# Y1BVER2_0_1.net
KiCad netlist of a schematic drawn in Altium Designer
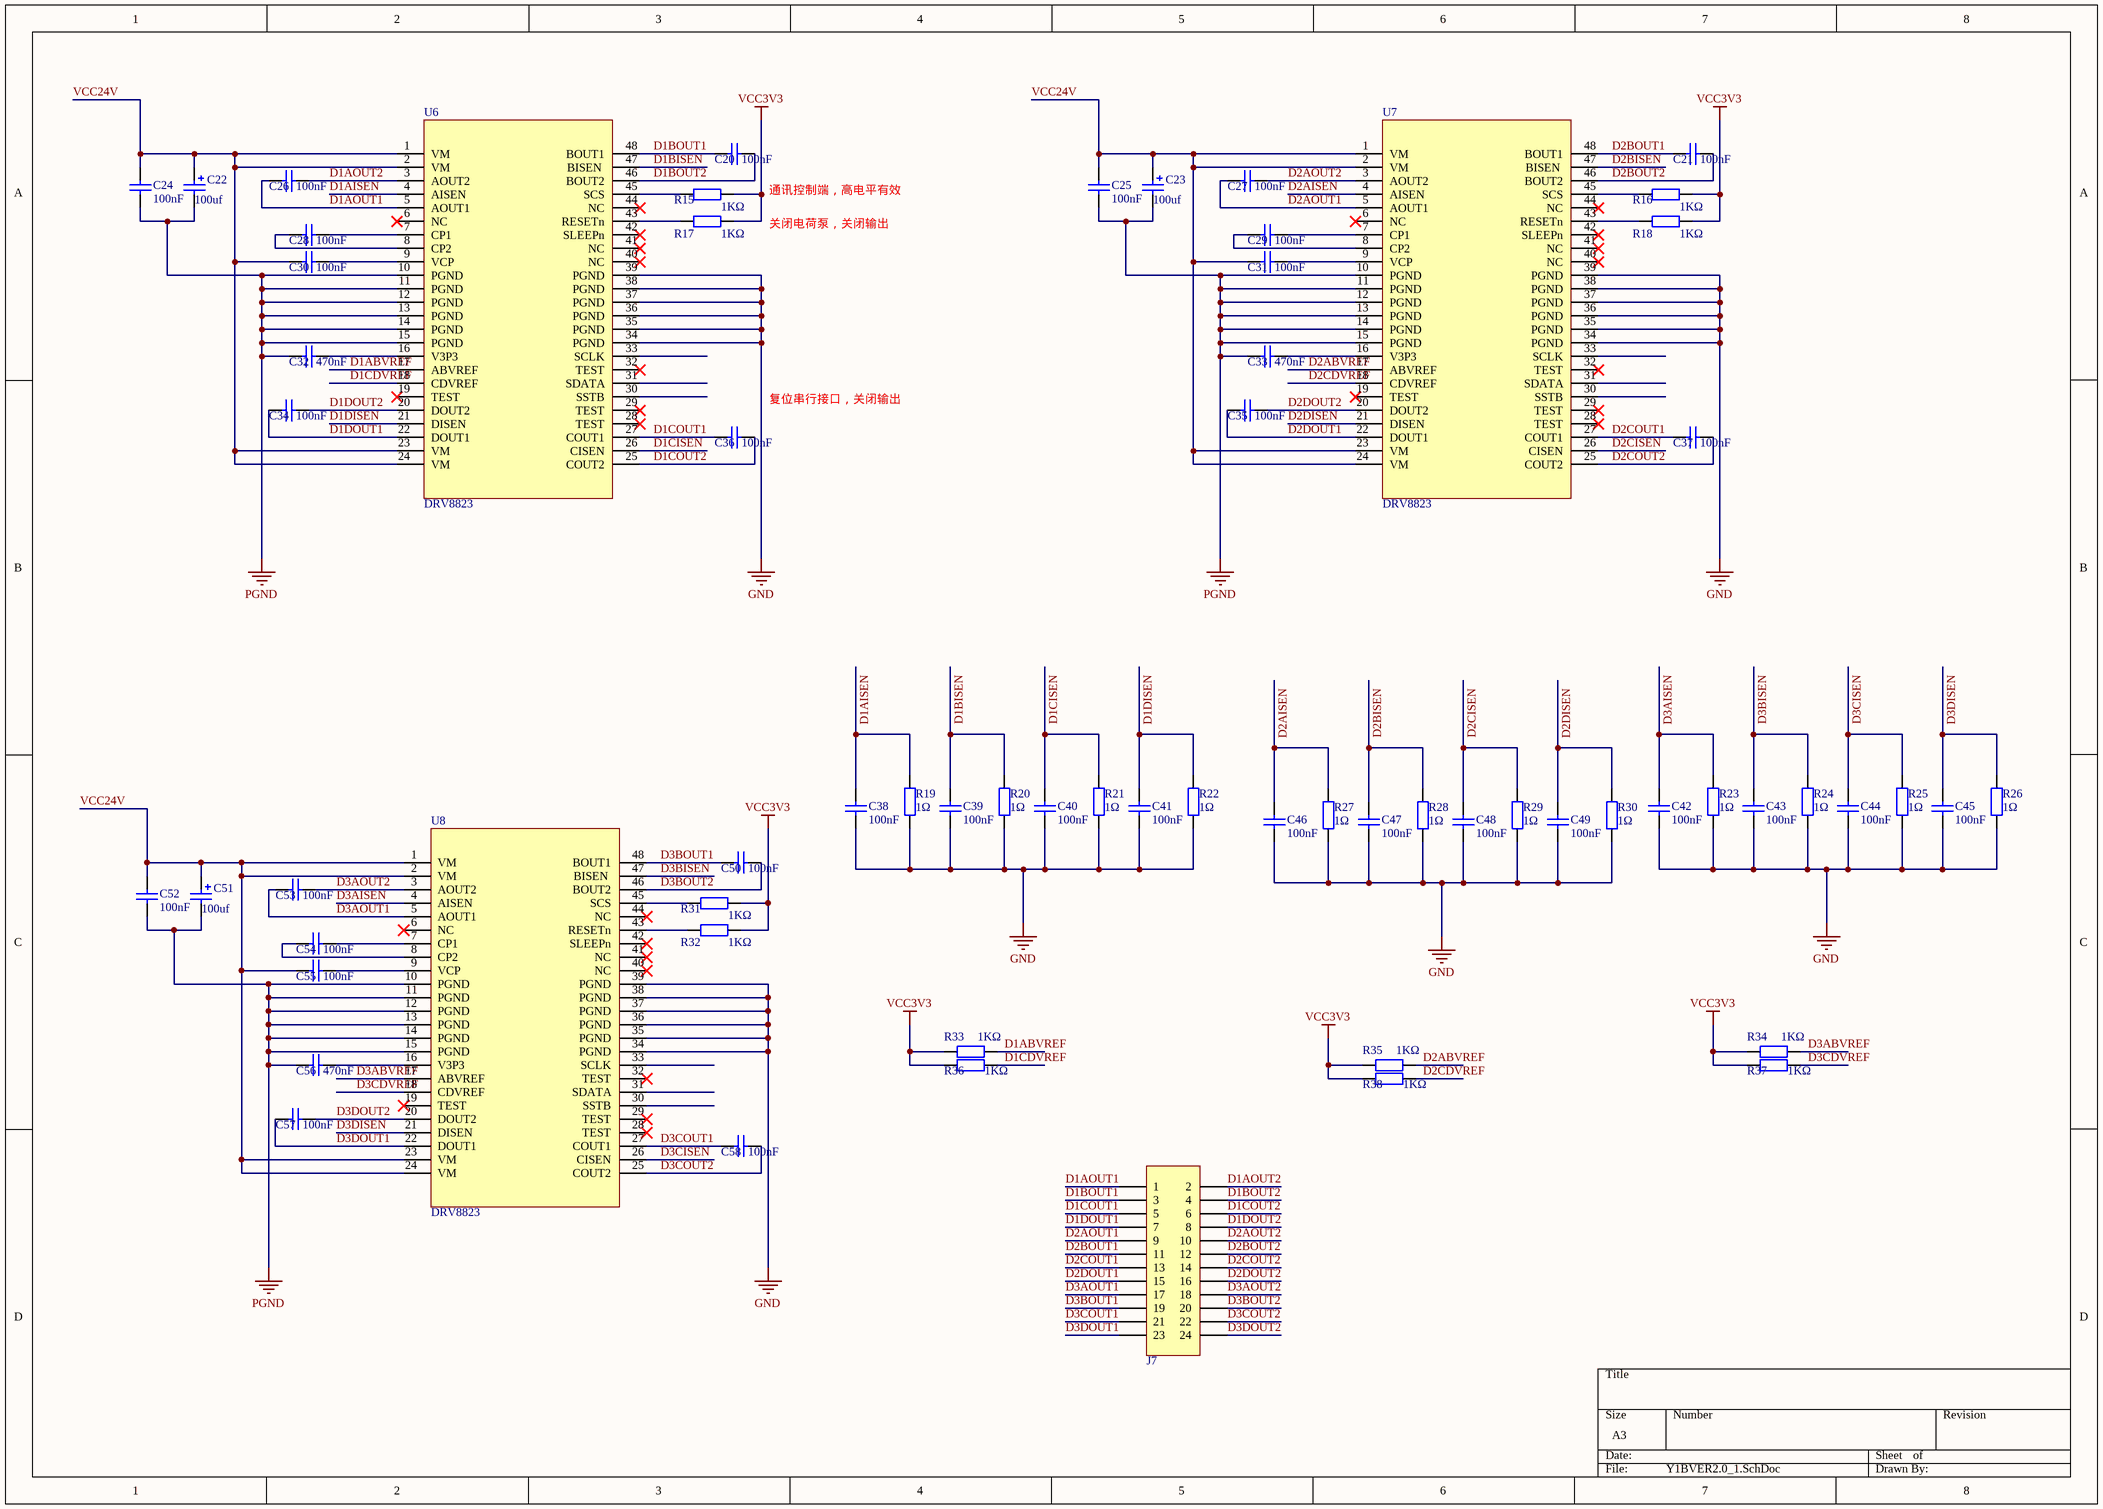
[diagram p0: Y1BVER2.0_1.SchDoc]

(export (version "E")
  (design (tool "Eeschema 10.0.6"))
  (components
    (comp (ref "C20")
      (value "100nF")
      (footprint "0603_C")
      (description "贴片电容")
      (libsource (lib "AD封装2018.9.19Miscellaneous Devices LC") (part "0603 100nF (104) 10% 50V"))
    )
    (comp (ref "C21")
      (value "100nF")
      (footprint "0603_C")
      (description "贴片电容")
      (libsource (lib "AD封装2018.9.19Miscellaneous Devices LC") (part "0603 100nF (104) 10% 50V"))
    )
    (comp (ref "C22") (value "100uf") (footprint "E_6.3*5.4") (libsource (lib "我的集成库") (part "C")))
    (comp (ref "C23") (value "100uf") (footprint "E_6.3*5.4") (libsource (lib "我的集成库") (part "C")))
    (comp (ref "C24")
      (value "100nF")
      (footprint "0603_C")
      (description "贴片电容")
      (libsource (lib "AD封装2018.9.19Miscellaneous Devices LC") (part "0603 100nF (104) 10% 50V"))
    )
    (comp (ref "C25")
      (value "100nF")
      (footprint "0603_C")
      (description "贴片电容")
      (libsource (lib "AD封装2018.9.19Miscellaneous Devices LC") (part "0603 100nF (104) 10% 50V"))
    )
    (comp (ref "C26")
      (value "100nF")
      (footprint "0603_C")
      (description "贴片电容")
      (libsource (lib "AD封装2018.9.19Miscellaneous Devices LC") (part "0603 100nF (104) 10% 50V"))
    )
    (comp (ref "C27")
      (value "100nF")
      (footprint "0603_C")
      (description "贴片电容")
      (libsource (lib "AD封装2018.9.19Miscellaneous Devices LC") (part "0603 100nF (104) 10% 50V"))
    )
    (comp (ref "C28")
      (value "100nF")
      (footprint "0603_C")
      (description "贴片电容")
      (libsource (lib "AD封装2018.9.19Miscellaneous Devices LC") (part "0603 100nF (104) 10% 50V"))
    )
    (comp (ref "C29")
      (value "100nF")
      (footprint "0603_C")
      (description "贴片电容")
      (libsource (lib "AD封装2018.9.19Miscellaneous Devices LC") (part "0603 100nF (104) 10% 50V"))
    )
    (comp (ref "C30")
      (value "100nF")
      (footprint "0603_C")
      (description "贴片电容")
      (libsource (lib "AD封装2018.9.19Miscellaneous Devices LC") (part "0603 100nF (104) 10% 50V"))
    )
    (comp (ref "C31")
      (value "100nF")
      (footprint "0603_C")
      (description "贴片电容")
      (libsource (lib "AD封装2018.9.19Miscellaneous Devices LC") (part "0603 100nF (104) 10% 50V"))
    )
    (comp (ref "C32")
      (value "470nF")
      (footprint "0603_C")
      (description "贴片电容")
      (libsource (lib "AD封装2018.9.19Miscellaneous Devices LC") (part "0603 470nF (474) 10% 25V"))
    )
    (comp (ref "C33")
      (value "470nF")
      (footprint "0603_C")
      (description "贴片电容")
      (libsource (lib "AD封装2018.9.19Miscellaneous Devices LC") (part "0603 470nF (474) 10% 25V"))
    )
    (comp (ref "C34")
      (value "100nF")
      (footprint "0603_C")
      (description "贴片电容")
      (libsource (lib "AD封装2018.9.19Miscellaneous Devices LC") (part "0603 100nF (104) 10% 50V"))
    )
    (comp (ref "C35")
      (value "100nF")
      (footprint "0603_C")
      (description "贴片电容")
      (libsource (lib "AD封装2018.9.19Miscellaneous Devices LC") (part "0603 100nF (104) 10% 50V"))
    )
    (comp (ref "C36")
      (value "100nF")
      (footprint "0603_C")
      (description "贴片电容")
      (libsource (lib "AD封装2018.9.19Miscellaneous Devices LC") (part "0603 100nF (104) 10% 50V"))
    )
    (comp (ref "C37")
      (value "100nF")
      (footprint "0603_C")
      (description "贴片电容")
      (libsource (lib "AD封装2018.9.19Miscellaneous Devices LC") (part "0603 100nF (104) 10% 50V"))
    )
    (comp (ref "C38")
      (value "100nF")
      (footprint "0603_C")
      (description "贴片电容")
      (libsource (lib "AD封装2018.9.19Miscellaneous Devices LC") (part "0603 100nF (104) 10% 50V"))
    )
    (comp (ref "C39")
      (value "100nF")
      (footprint "0603_C")
      (description "贴片电容")
      (libsource (lib "AD封装2018.9.19Miscellaneous Devices LC") (part "0603 100nF (104) 10% 50V"))
    )
    (comp (ref "C40")
      (value "100nF")
      (footprint "0603_C")
      (description "贴片电容")
      (libsource (lib "AD封装2018.9.19Miscellaneous Devices LC") (part "0603 100nF (104) 10% 50V"))
    )
    (comp (ref "C41")
      (value "100nF")
      (footprint "0603_C")
      (description "贴片电容")
      (libsource (lib "AD封装2018.9.19Miscellaneous Devices LC") (part "0603 100nF (104) 10% 50V"))
    )
    (comp (ref "C42")
      (value "100nF")
      (footprint "0603_C")
      (description "贴片电容")
      (libsource (lib "AD封装2018.9.19Miscellaneous Devices LC") (part "0603 100nF (104) 10% 50V"))
    )
    (comp (ref "C43")
      (value "100nF")
      (footprint "0603_C")
      (description "贴片电容")
      (libsource (lib "AD封装2018.9.19Miscellaneous Devices LC") (part "0603 100nF (104) 10% 50V"))
    )
    (comp (ref "C44")
      (value "100nF")
      (footprint "0603_C")
      (description "贴片电容")
      (libsource (lib "AD封装2018.9.19Miscellaneous Devices LC") (part "0603 100nF (104) 10% 50V"))
    )
    (comp (ref "C45")
      (value "100nF")
      (footprint "0603_C")
      (description "贴片电容")
      (libsource (lib "AD封装2018.9.19Miscellaneous Devices LC") (part "0603 100nF (104) 10% 50V"))
    )
    (comp (ref "C46")
      (value "100nF")
      (footprint "0603_C")
      (description "贴片电容")
      (libsource (lib "AD封装2018.9.19Miscellaneous Devices LC") (part "0603 100nF (104) 10% 50V"))
    )
    (comp (ref "C47")
      (value "100nF")
      (footprint "0603_C")
      (description "贴片电容")
      (libsource (lib "AD封装2018.9.19Miscellaneous Devices LC") (part "0603 100nF (104) 10% 50V"))
    )
    (comp (ref "C48")
      (value "100nF")
      (footprint "0603_C")
      (description "贴片电容")
      (libsource (lib "AD封装2018.9.19Miscellaneous Devices LC") (part "0603 100nF (104) 10% 50V"))
    )
    (comp (ref "C49")
      (value "100nF")
      (footprint "0603_C")
      (description "贴片电容")
      (libsource (lib "AD封装2018.9.19Miscellaneous Devices LC") (part "0603 100nF (104) 10% 50V"))
    )
    (comp (ref "C50")
      (value "100nF")
      (footprint "0603_C")
      (description "贴片电容")
      (libsource (lib "AD封装2018.9.19Miscellaneous Devices LC") (part "0603 100nF (104) 10% 50V"))
    )
    (comp (ref "C51") (value "100uf") (footprint "E_6.3*5.4") (libsource (lib "我的集成库") (part "C")))
    (comp (ref "C52")
      (value "100nF")
      (footprint "0603_C")
      (description "贴片电容")
      (libsource (lib "AD封装2018.9.19Miscellaneous Devices LC") (part "0603 100nF (104) 10% 50V"))
    )
    (comp (ref "C53")
      (value "100nF")
      (footprint "0603_C")
      (description "贴片电容")
      (libsource (lib "AD封装2018.9.19Miscellaneous Devices LC") (part "0603 100nF (104) 10% 50V"))
    )
    (comp (ref "C54")
      (value "100nF")
      (footprint "0603_C")
      (description "贴片电容")
      (libsource (lib "AD封装2018.9.19Miscellaneous Devices LC") (part "0603 100nF (104) 10% 50V"))
    )
    (comp (ref "C55")
      (value "100nF")
      (footprint "0603_C")
      (description "贴片电容")
      (libsource (lib "AD封装2018.9.19Miscellaneous Devices LC") (part "0603 100nF (104) 10% 50V"))
    )
    (comp (ref "C56")
      (value "470nF")
      (footprint "0603_C")
      (description "贴片电容")
      (libsource (lib "AD封装2018.9.19Miscellaneous Devices LC") (part "0603 470nF (474) 10% 25V"))
    )
    (comp (ref "C57")
      (value "100nF")
      (footprint "0603_C")
      (description "贴片电容")
      (libsource (lib "AD封装2018.9.19Miscellaneous Devices LC") (part "0603 100nF (104) 10% 50V"))
    )
    (comp (ref "C58")
      (value "100nF")
      (footprint "0603_C")
      (description "贴片电容")
      (libsource (lib "AD封装2018.9.19Miscellaneous Devices LC") (part "0603 100nF (104) 10% 50V"))
    )
    (comp (ref "J7")
      (value "header24p")
      (footprint "5557-2*12P")
      (libsource (lib "我的集成库") (part "header24p"))
    )
    (comp (ref "R15")
      (value "1KΩ")
      (footprint "0603_R")
      (description "贴片电阻")
      (libsource (lib "AD封装2018.9.19Miscellaneous Devices LC") (part "0603 1KΩ (1001) 1%"))
    )
    (comp (ref "R16")
      (value "1KΩ")
      (footprint "0603_R")
      (description "贴片电阻")
      (libsource (lib "AD封装2018.9.19Miscellaneous Devices LC") (part "0603 1KΩ (1001) 1%"))
    )
    (comp (ref "R17")
      (value "1KΩ")
      (footprint "0603_R")
      (description "贴片电阻")
      (libsource (lib "AD封装2018.9.19Miscellaneous Devices LC") (part "0603 1KΩ (1001) 1%"))
    )
    (comp (ref "R18")
      (value "1KΩ")
      (footprint "0603_R")
      (description "贴片电阻")
      (libsource (lib "AD封装2018.9.19Miscellaneous Devices LC") (part "0603 1KΩ (1001) 1%"))
    )
    (comp (ref "R19")
      (value "1Ω")
      (footprint "0603_R")
      (description "贴片电阻")
      (libsource (lib "AD封装2018.9.19Miscellaneous Devices LC") (part "0603 1Ω (1R00) 1%"))
    )
    (comp (ref "R20")
      (value "1Ω")
      (footprint "0603_R")
      (description "贴片电阻")
      (libsource (lib "AD封装2018.9.19Miscellaneous Devices LC") (part "0603 1Ω (1R00) 1%"))
    )
    (comp (ref "R21")
      (value "1Ω")
      (footprint "0603_R")
      (description "贴片电阻")
      (libsource (lib "AD封装2018.9.19Miscellaneous Devices LC") (part "0603 1Ω (1R00) 1%"))
    )
    (comp (ref "R22")
      (value "1Ω")
      (footprint "0603_R")
      (description "贴片电阻")
      (libsource (lib "AD封装2018.9.19Miscellaneous Devices LC") (part "0603 1Ω (1R00) 1%"))
    )
    (comp (ref "R23")
      (value "1Ω")
      (footprint "0603_R")
      (description "贴片电阻")
      (libsource (lib "AD封装2018.9.19Miscellaneous Devices LC") (part "0603 1Ω (1R00) 1%"))
    )
    (comp (ref "R24")
      (value "1Ω")
      (footprint "0603_R")
      (description "贴片电阻")
      (libsource (lib "AD封装2018.9.19Miscellaneous Devices LC") (part "0603 1Ω (1R00) 1%"))
    )
    (comp (ref "R25")
      (value "1Ω")
      (footprint "0603_R")
      (description "贴片电阻")
      (libsource (lib "AD封装2018.9.19Miscellaneous Devices LC") (part "0603 1Ω (1R00) 1%"))
    )
    (comp (ref "R26")
      (value "1Ω")
      (footprint "0603_R")
      (description "贴片电阻")
      (libsource (lib "AD封装2018.9.19Miscellaneous Devices LC") (part "0603 1Ω (1R00) 1%"))
    )
    (comp (ref "R27")
      (value "1Ω")
      (footprint "0603_R")
      (description "贴片电阻")
      (libsource (lib "AD封装2018.9.19Miscellaneous Devices LC") (part "0603 1Ω (1R00) 1%"))
    )
    (comp (ref "R28")
      (value "1Ω")
      (footprint "0603_R")
      (description "贴片电阻")
      (libsource (lib "AD封装2018.9.19Miscellaneous Devices LC") (part "0603 1Ω (1R00) 1%"))
    )
    (comp (ref "R29")
      (value "1Ω")
      (footprint "0603_R")
      (description "贴片电阻")
      (libsource (lib "AD封装2018.9.19Miscellaneous Devices LC") (part "0603 1Ω (1R00) 1%"))
    )
    (comp (ref "R30")
      (value "1Ω")
      (footprint "0603_R")
      (description "贴片电阻")
      (libsource (lib "AD封装2018.9.19Miscellaneous Devices LC") (part "0603 1Ω (1R00) 1%"))
    )
    (comp (ref "R31")
      (value "1KΩ")
      (footprint "0603_R")
      (description "贴片电阻")
      (libsource (lib "AD封装2018.9.19Miscellaneous Devices LC") (part "0603 1KΩ (1001) 1%"))
    )
    (comp (ref "R32")
      (value "1KΩ")
      (footprint "0603_R")
      (description "贴片电阻")
      (libsource (lib "AD封装2018.9.19Miscellaneous Devices LC") (part "0603 1KΩ (1001) 1%"))
    )
    (comp (ref "R33")
      (value "1KΩ")
      (footprint "0603_R")
      (description "贴片电阻")
      (libsource (lib "AD封装2018.9.19Miscellaneous Devices LC") (part "0603 1KΩ (1001) 1%"))
    )
    (comp (ref "R34")
      (value "1KΩ")
      (footprint "0603_R")
      (description "贴片电阻")
      (libsource (lib "AD封装2018.9.19Miscellaneous Devices LC") (part "0603 1KΩ (1001) 1%"))
    )
    (comp (ref "R35")
      (value "1KΩ")
      (footprint "0603_R")
      (description "贴片电阻")
      (libsource (lib "AD封装2018.9.19Miscellaneous Devices LC") (part "0603 1KΩ (1001) 1%"))
    )
    (comp (ref "R36")
      (value "1KΩ")
      (footprint "0603_R")
      (description "贴片电阻")
      (libsource (lib "AD封装2018.9.19Miscellaneous Devices LC") (part "0603 1KΩ (1001) 1%"))
    )
    (comp (ref "R37")
      (value "1KΩ")
      (footprint "0603_R")
      (description "贴片电阻")
      (libsource (lib "AD封装2018.9.19Miscellaneous Devices LC") (part "0603 1KΩ (1001) 1%"))
    )
    (comp (ref "R38")
      (value "1KΩ")
      (footprint "0603_R")
      (description "贴片电阻")
      (libsource (lib "AD封装2018.9.19Miscellaneous Devices LC") (part "0603 1KΩ (1001) 1%"))
    )
    (comp (ref "U6")
      (value "DRV8823")
      (footprint "HTSSOP-48")
      (description "4路BDC电机驱动")
      (libsource (lib "我的原理图库") (part "DRV8823"))
    )
    (comp (ref "U7")
      (value "DRV8823")
      (footprint "HTSSOP-48")
      (description "4路BDC电机驱动")
      (libsource (lib "我的原理图库") (part "DRV8823"))
    )
    (comp (ref "U8")
      (value "DRV8823")
      (footprint "HTSSOP-48")
      (description "4路BDC电机驱动")
      (libsource (lib "我的原理图库") (part "DRV8823"))
    )
  )
  (nets
    (net (code "1") (name "/D1ABVREF") (class "Default")
      (node (ref "R33") (pin "2") (pinfunction "2_2") (pintype "passive"))
      (node (ref "U6") (pin "17") (pinfunction "ABVREF_17") (pintype "passive"))
    )
    (net (code "2") (name "/D1AISEN") (class "Default")
      (node (ref "C38") (pin "2") (pinfunction "2_2") (pintype "passive"))
      (node (ref "R19") (pin "2") (pinfunction "2_2") (pintype "passive"))
      (node (ref "U6") (pin "4") (pinfunction "AISEN_4") (pintype "passive"))
    )
    (net (code "3") (name "/D1AOUT1") (class "Default")
      (node (ref "C26") (pin "1") (pinfunction "1_1") (pintype "passive"))
      (node (ref "J7") (pin "1") (pinfunction "1_1") (pintype "passive"))
      (node (ref "U6") (pin "5") (pinfunction "AOUT1_5") (pintype "passive"))
    )
    (net (code "4") (name "/D1AOUT2") (class "Default")
      (node (ref "C26") (pin "2") (pinfunction "2_2") (pintype "passive"))
      (node (ref "J7") (pin "2") (pinfunction "2_2") (pintype "passive"))
      (node (ref "U6") (pin "3") (pinfunction "AOUT2_3") (pintype "passive"))
    )
    (net (code "5") (name "/D1BISEN") (class "Default")
      (node (ref "C39") (pin "2") (pinfunction "2_2") (pintype "passive"))
      (node (ref "R20") (pin "2") (pinfunction "2_2") (pintype "passive"))
      (node (ref "U6") (pin "47") (pinfunction "BISEN_47") (pintype "passive"))
    )
    (net (code "6") (name "/D1BOUT1") (class "Default")
      (node (ref "C20") (pin "1") (pinfunction "1_1") (pintype "passive"))
      (node (ref "J7") (pin "3") (pinfunction "3_3") (pintype "passive"))
      (node (ref "U6") (pin "48") (pinfunction "BOUT1_48") (pintype "passive"))
    )
    (net (code "7") (name "/D1BOUT2") (class "Default")
      (node (ref "C20") (pin "2") (pinfunction "2_2") (pintype "passive"))
      (node (ref "J7") (pin "4") (pinfunction "4_4") (pintype "passive"))
      (node (ref "U6") (pin "46") (pinfunction "BOUT2_46") (pintype "passive"))
    )
    (net (code "8") (name "/D1CDVREF") (class "Default")
      (node (ref "R36") (pin "2") (pinfunction "2_2") (pintype "passive"))
      (node (ref "U6") (pin "18") (pinfunction "CDVREF_18") (pintype "passive"))
    )
    (net (code "9") (name "/D1CISEN") (class "Default")
      (node (ref "C40") (pin "2") (pinfunction "2_2") (pintype "passive"))
      (node (ref "R21") (pin "2") (pinfunction "2_2") (pintype "passive"))
      (node (ref "U6") (pin "26") (pinfunction "CISEN_26") (pintype "passive"))
    )
    (net (code "10") (name "/D1COUT1") (class "Default")
      (node (ref "C36") (pin "1") (pinfunction "1_1") (pintype "passive"))
      (node (ref "J7") (pin "5") (pinfunction "5_5") (pintype "passive"))
      (node (ref "U6") (pin "27") (pinfunction "COUT1_27") (pintype "passive"))
    )
    (net (code "11") (name "/D1COUT2") (class "Default")
      (node (ref "C36") (pin "2") (pinfunction "2_2") (pintype "passive"))
      (node (ref "J7") (pin "6") (pinfunction "6_6") (pintype "passive"))
      (node (ref "U6") (pin "25") (pinfunction "COUT2_25") (pintype "passive"))
    )
    (net (code "12") (name "/D1DISEN") (class "Default")
      (node (ref "C41") (pin "2") (pinfunction "2_2") (pintype "passive"))
      (node (ref "R22") (pin "2") (pinfunction "2_2") (pintype "passive"))
      (node (ref "U6") (pin "21") (pinfunction "DISEN_21") (pintype "passive"))
    )
    (net (code "13") (name "/D1DOUT1") (class "Default")
      (node (ref "C34") (pin "1") (pinfunction "1_1") (pintype "passive"))
      (node (ref "J7") (pin "7") (pinfunction "7_7") (pintype "passive"))
      (node (ref "U6") (pin "22") (pinfunction "DOUT1_22") (pintype "passive"))
    )
    (net (code "14") (name "/D1DOUT2") (class "Default")
      (node (ref "C34") (pin "2") (pinfunction "2_2") (pintype "passive"))
      (node (ref "J7") (pin "8") (pinfunction "8_8") (pintype "passive"))
      (node (ref "U6") (pin "20") (pinfunction "DOUT2_20") (pintype "passive"))
    )
    (net (code "15") (name "/D2ABVREF") (class "Default")
      (node (ref "R35") (pin "2") (pinfunction "2_2") (pintype "passive"))
      (node (ref "U7") (pin "17") (pinfunction "ABVREF_17") (pintype "passive"))
    )
    (net (code "16") (name "/D2AISEN") (class "Default")
      (node (ref "C46") (pin "2") (pinfunction "2_2") (pintype "passive"))
      (node (ref "R27") (pin "2") (pinfunction "2_2") (pintype "passive"))
      (node (ref "U7") (pin "4") (pinfunction "AISEN_4") (pintype "passive"))
    )
    (net (code "17") (name "/D2AOUT1") (class "Default")
      (node (ref "C27") (pin "1") (pinfunction "1_1") (pintype "passive"))
      (node (ref "J7") (pin "9") (pinfunction "9_9") (pintype "passive"))
      (node (ref "U7") (pin "5") (pinfunction "AOUT1_5") (pintype "passive"))
    )
    (net (code "18") (name "/D2AOUT2") (class "Default")
      (node (ref "C27") (pin "2") (pinfunction "2_2") (pintype "passive"))
      (node (ref "J7") (pin "10") (pinfunction "10_10") (pintype "passive"))
      (node (ref "U7") (pin "3") (pinfunction "AOUT2_3") (pintype "passive"))
    )
    (net (code "19") (name "/D2BISEN") (class "Default")
      (node (ref "C47") (pin "2") (pinfunction "2_2") (pintype "passive"))
      (node (ref "R28") (pin "2") (pinfunction "2_2") (pintype "passive"))
      (node (ref "U7") (pin "47") (pinfunction "BISEN_47") (pintype "passive"))
    )
    (net (code "20") (name "/D2BOUT1") (class "Default")
      (node (ref "C21") (pin "1") (pinfunction "1_1") (pintype "passive"))
      (node (ref "J7") (pin "11") (pinfunction "11_11") (pintype "passive"))
      (node (ref "U7") (pin "48") (pinfunction "BOUT1_48") (pintype "passive"))
    )
    (net (code "21") (name "/D2BOUT2") (class "Default")
      (node (ref "C21") (pin "2") (pinfunction "2_2") (pintype "passive"))
      (node (ref "J7") (pin "12") (pinfunction "12_12") (pintype "passive"))
      (node (ref "U7") (pin "46") (pinfunction "BOUT2_46") (pintype "passive"))
    )
    (net (code "22") (name "/D2CDVREF") (class "Default")
      (node (ref "R38") (pin "2") (pinfunction "2_2") (pintype "passive"))
      (node (ref "U7") (pin "18") (pinfunction "CDVREF_18") (pintype "passive"))
    )
    (net (code "23") (name "/D2CISEN") (class "Default")
      (node (ref "C48") (pin "2") (pinfunction "2_2") (pintype "passive"))
      (node (ref "R29") (pin "2") (pinfunction "2_2") (pintype "passive"))
      (node (ref "U7") (pin "26") (pinfunction "CISEN_26") (pintype "passive"))
    )
    (net (code "24") (name "/D2COUT1") (class "Default")
      (node (ref "C37") (pin "1") (pinfunction "1_1") (pintype "passive"))
      (node (ref "J7") (pin "13") (pinfunction "13_13") (pintype "passive"))
      (node (ref "U7") (pin "27") (pinfunction "COUT1_27") (pintype "passive"))
    )
    (net (code "25") (name "/D2COUT2") (class "Default")
      (node (ref "C37") (pin "2") (pinfunction "2_2") (pintype "passive"))
      (node (ref "J7") (pin "14") (pinfunction "14_14") (pintype "passive"))
      (node (ref "U7") (pin "25") (pinfunction "COUT2_25") (pintype "passive"))
    )
    (net (code "26") (name "/D2DISEN") (class "Default")
      (node (ref "C49") (pin "2") (pinfunction "2_2") (pintype "passive"))
      (node (ref "R30") (pin "2") (pinfunction "2_2") (pintype "passive"))
      (node (ref "U7") (pin "21") (pinfunction "DISEN_21") (pintype "passive"))
    )
    (net (code "27") (name "/D2DOUT1") (class "Default")
      (node (ref "C35") (pin "1") (pinfunction "1_1") (pintype "passive"))
      (node (ref "J7") (pin "15") (pinfunction "15_15") (pintype "passive"))
      (node (ref "U7") (pin "22") (pinfunction "DOUT1_22") (pintype "passive"))
    )
    (net (code "28") (name "/D2DOUT2") (class "Default")
      (node (ref "C35") (pin "2") (pinfunction "2_2") (pintype "passive"))
      (node (ref "J7") (pin "16") (pinfunction "16_16") (pintype "passive"))
      (node (ref "U7") (pin "20") (pinfunction "DOUT2_20") (pintype "passive"))
    )
    (net (code "29") (name "/D3ABVREF") (class "Default")
      (node (ref "R34") (pin "2") (pinfunction "2_2") (pintype "passive"))
      (node (ref "U8") (pin "17") (pinfunction "ABVREF_17") (pintype "passive"))
    )
    (net (code "30") (name "/D3AISEN") (class "Default")
      (node (ref "C42") (pin "2") (pinfunction "2_2") (pintype "passive"))
      (node (ref "R23") (pin "2") (pinfunction "2_2") (pintype "passive"))
      (node (ref "U8") (pin "4") (pinfunction "AISEN_4") (pintype "passive"))
    )
    (net (code "31") (name "/D3AOUT1") (class "Default")
      (node (ref "C53") (pin "1") (pinfunction "1_1") (pintype "passive"))
      (node (ref "J7") (pin "17") (pinfunction "17_17") (pintype "passive"))
      (node (ref "U8") (pin "5") (pinfunction "AOUT1_5") (pintype "passive"))
    )
    (net (code "32") (name "/D3AOUT2") (class "Default")
      (node (ref "C53") (pin "2") (pinfunction "2_2") (pintype "passive"))
      (node (ref "J7") (pin "18") (pinfunction "18_18") (pintype "passive"))
      (node (ref "U8") (pin "3") (pinfunction "AOUT2_3") (pintype "passive"))
    )
    (net (code "33") (name "/D3BISEN") (class "Default")
      (node (ref "C43") (pin "2") (pinfunction "2_2") (pintype "passive"))
      (node (ref "R24") (pin "2") (pinfunction "2_2") (pintype "passive"))
      (node (ref "U8") (pin "47") (pinfunction "BISEN_47") (pintype "passive"))
    )
    (net (code "34") (name "/D3BOUT1") (class "Default")
      (node (ref "C50") (pin "1") (pinfunction "1_1") (pintype "passive"))
      (node (ref "J7") (pin "19") (pinfunction "19_19") (pintype "passive"))
      (node (ref "U8") (pin "48") (pinfunction "BOUT1_48") (pintype "passive"))
    )
    (net (code "35") (name "/D3BOUT2") (class "Default")
      (node (ref "C50") (pin "2") (pinfunction "2_2") (pintype "passive"))
      (node (ref "J7") (pin "20") (pinfunction "20_20") (pintype "passive"))
      (node (ref "U8") (pin "46") (pinfunction "BOUT2_46") (pintype "passive"))
    )
    (net (code "36") (name "/D3CDVREF") (class "Default")
      (node (ref "R37") (pin "2") (pinfunction "2_2") (pintype "passive"))
      (node (ref "U8") (pin "18") (pinfunction "CDVREF_18") (pintype "passive"))
    )
    (net (code "37") (name "/D3CISEN") (class "Default")
      (node (ref "C44") (pin "2") (pinfunction "2_2") (pintype "passive"))
      (node (ref "R25") (pin "2") (pinfunction "2_2") (pintype "passive"))
      (node (ref "U8") (pin "26") (pinfunction "CISEN_26") (pintype "passive"))
    )
    (net (code "38") (name "/D3COUT1") (class "Default")
      (node (ref "C58") (pin "1") (pinfunction "1_1") (pintype "passive"))
      (node (ref "J7") (pin "21") (pinfunction "21_21") (pintype "passive"))
      (node (ref "U8") (pin "27") (pinfunction "COUT1_27") (pintype "passive"))
    )
    (net (code "39") (name "/D3COUT2") (class "Default")
      (node (ref "C58") (pin "2") (pinfunction "2_2") (pintype "passive"))
      (node (ref "J7") (pin "22") (pinfunction "22_22") (pintype "passive"))
      (node (ref "U8") (pin "25") (pinfunction "COUT2_25") (pintype "passive"))
    )
    (net (code "40") (name "/D3DISEN") (class "Default")
      (node (ref "C45") (pin "2") (pinfunction "2_2") (pintype "passive"))
      (node (ref "R26") (pin "2") (pinfunction "2_2") (pintype "passive"))
      (node (ref "U8") (pin "21") (pinfunction "DISEN_21") (pintype "passive"))
    )
    (net (code "41") (name "/D3DOUT1") (class "Default")
      (node (ref "C57") (pin "1") (pinfunction "1_1") (pintype "passive"))
      (node (ref "J7") (pin "23") (pinfunction "23_23") (pintype "passive"))
      (node (ref "U8") (pin "22") (pinfunction "DOUT1_22") (pintype "passive"))
    )
    (net (code "42") (name "/D3DOUT2") (class "Default")
      (node (ref "C57") (pin "2") (pinfunction "2_2") (pintype "passive"))
      (node (ref "J7") (pin "24") (pinfunction "24_24") (pintype "passive"))
      (node (ref "U8") (pin "20") (pinfunction "DOUT2_20") (pintype "passive"))
    )
    (net (code "43") (name "/VCC24V") (class "Default")
      (node (ref "C22") (pin "1") (pinfunction "1_1") (pintype "passive"))
      (node (ref "C23") (pin "1") (pinfunction "1_1") (pintype "passive"))
      (node (ref "C24") (pin "2") (pinfunction "2_2") (pintype "passive"))
      (node (ref "C25") (pin "2") (pinfunction "2_2") (pintype "passive"))
      (node (ref "C30") (pin "1") (pinfunction "1_1") (pintype "passive"))
      (node (ref "C31") (pin "1") (pinfunction "1_1") (pintype "passive"))
      (node (ref "C51") (pin "1") (pinfunction "1_1") (pintype "passive"))
      (node (ref "C52") (pin "2") (pinfunction "2_2") (pintype "passive"))
      (node (ref "C55") (pin "1") (pinfunction "1_1") (pintype "passive"))
      (node (ref "U6") (pin "1") (pinfunction "VM_1") (pintype "passive"))
      (node (ref "U6") (pin "2") (pinfunction "VM_2") (pintype "passive"))
      (node (ref "U6") (pin "23") (pinfunction "VM_23") (pintype "passive"))
      (node (ref "U6") (pin "24") (pinfunction "VM_24") (pintype "passive"))
      (node (ref "U7") (pin "1") (pinfunction "VM_1") (pintype "passive"))
      (node (ref "U7") (pin "2") (pinfunction "VM_2") (pintype "passive"))
      (node (ref "U7") (pin "23") (pinfunction "VM_23") (pintype "passive"))
      (node (ref "U7") (pin "24") (pinfunction "VM_24") (pintype "passive"))
      (node (ref "U8") (pin "1") (pinfunction "VM_1") (pintype "passive"))
      (node (ref "U8") (pin "2") (pinfunction "VM_2") (pintype "passive"))
      (node (ref "U8") (pin "23") (pinfunction "VM_23") (pintype "passive"))
      (node (ref "U8") (pin "24") (pinfunction "VM_24") (pintype "passive"))
    )
    (net (code "44") (name "GND") (class "Default")
      (node (ref "C38") (pin "1") (pinfunction "1_1") (pintype "passive"))
      (node (ref "C39") (pin "1") (pinfunction "1_1") (pintype "passive"))
      (node (ref "C40") (pin "1") (pinfunction "1_1") (pintype "passive"))
      (node (ref "C41") (pin "1") (pinfunction "1_1") (pintype "passive"))
      (node (ref "C42") (pin "1") (pinfunction "1_1") (pintype "passive"))
      (node (ref "C43") (pin "1") (pinfunction "1_1") (pintype "passive"))
      (node (ref "C44") (pin "1") (pinfunction "1_1") (pintype "passive"))
      (node (ref "C45") (pin "1") (pinfunction "1_1") (pintype "passive"))
      (node (ref "C46") (pin "1") (pinfunction "1_1") (pintype "passive"))
      (node (ref "C47") (pin "1") (pinfunction "1_1") (pintype "passive"))
      (node (ref "C48") (pin "1") (pinfunction "1_1") (pintype "passive"))
      (node (ref "C49") (pin "1") (pinfunction "1_1") (pintype "passive"))
      (node (ref "R19") (pin "1") (pinfunction "1_1") (pintype "passive"))
      (node (ref "R20") (pin "1") (pinfunction "1_1") (pintype "passive"))
      (node (ref "R21") (pin "1") (pinfunction "1_1") (pintype "passive"))
      (node (ref "R22") (pin "1") (pinfunction "1_1") (pintype "passive"))
      (node (ref "R23") (pin "1") (pinfunction "1_1") (pintype "passive"))
      (node (ref "R24") (pin "1") (pinfunction "1_1") (pintype "passive"))
      (node (ref "R25") (pin "1") (pinfunction "1_1") (pintype "passive"))
      (node (ref "R26") (pin "1") (pinfunction "1_1") (pintype "passive"))
      (node (ref "R27") (pin "1") (pinfunction "1_1") (pintype "passive"))
      (node (ref "R28") (pin "1") (pinfunction "1_1") (pintype "passive"))
      (node (ref "R29") (pin "1") (pinfunction "1_1") (pintype "passive"))
      (node (ref "R30") (pin "1") (pinfunction "1_1") (pintype "passive"))
      (node (ref "U6") (pin "34") (pinfunction "PGND_34") (pintype "passive"))
      (node (ref "U6") (pin "35") (pinfunction "PGND_35") (pintype "passive"))
      (node (ref "U6") (pin "36") (pinfunction "PGND_36") (pintype "passive"))
      (node (ref "U6") (pin "37") (pinfunction "PGND_37") (pintype "passive"))
      (node (ref "U6") (pin "38") (pinfunction "PGND_38") (pintype "passive"))
      (node (ref "U6") (pin "39") (pinfunction "PGND_39") (pintype "passive"))
      (node (ref "U7") (pin "34") (pinfunction "PGND_34") (pintype "passive"))
      (node (ref "U7") (pin "35") (pinfunction "PGND_35") (pintype "passive"))
      (node (ref "U7") (pin "36") (pinfunction "PGND_36") (pintype "passive"))
      (node (ref "U7") (pin "37") (pinfunction "PGND_37") (pintype "passive"))
      (node (ref "U7") (pin "38") (pinfunction "PGND_38") (pintype "passive"))
      (node (ref "U7") (pin "39") (pinfunction "PGND_39") (pintype "passive"))
      (node (ref "U8") (pin "34") (pinfunction "PGND_34") (pintype "passive"))
      (node (ref "U8") (pin "35") (pinfunction "PGND_35") (pintype "passive"))
      (node (ref "U8") (pin "36") (pinfunction "PGND_36") (pintype "passive"))
      (node (ref "U8") (pin "37") (pinfunction "PGND_37") (pintype "passive"))
      (node (ref "U8") (pin "38") (pinfunction "PGND_38") (pintype "passive"))
      (node (ref "U8") (pin "39") (pinfunction "PGND_39") (pintype "passive"))
    )
    (net (code "45") (name "Net-(U6-CP1)") (class "Default")
      (node (ref "C28") (pin "2") (pinfunction "2_2") (pintype "passive"))
      (node (ref "U6") (pin "7") (pinfunction "CP1_7") (pintype "passive"))
    )
    (net (code "46") (name "Net-(U6-CP2)") (class "Default")
      (node (ref "C28") (pin "1") (pinfunction "1_1") (pintype "passive"))
      (node (ref "U6") (pin "8") (pinfunction "CP2_8") (pintype "passive"))
    )
    (net (code "47") (name "Net-(U6-RESETn)") (class "Default")
      (node (ref "R17") (pin "1") (pinfunction "1_1") (pintype "passive"))
      (node (ref "U6") (pin "43") (pinfunction "RESETn_43") (pintype "passive"))
    )
    (net (code "48") (name "Net-(U6-SCS)") (class "Default")
      (node (ref "R15") (pin "1") (pinfunction "1_1") (pintype "passive"))
      (node (ref "U6") (pin "45") (pinfunction "SCS_45") (pintype "passive"))
    )
    (net (code "49") (name "Net-(U6-V3P3)") (class "Default")
      (node (ref "C32") (pin "2") (pinfunction "2_2") (pintype "passive"))
      (node (ref "U6") (pin "16") (pinfunction "V3P3_16") (pintype "passive"))
    )
    (net (code "50") (name "Net-(U6-VCP)") (class "Default")
      (node (ref "C30") (pin "2") (pinfunction "2_2") (pintype "passive"))
      (node (ref "U6") (pin "9") (pinfunction "VCP_9") (pintype "passive"))
    )
    (net (code "51") (name "Net-(U7-CP1)") (class "Default")
      (node (ref "C29") (pin "2") (pinfunction "2_2") (pintype "passive"))
      (node (ref "U7") (pin "7") (pinfunction "CP1_7") (pintype "passive"))
    )
    (net (code "52") (name "Net-(U7-CP2)") (class "Default")
      (node (ref "C29") (pin "1") (pinfunction "1_1") (pintype "passive"))
      (node (ref "U7") (pin "8") (pinfunction "CP2_8") (pintype "passive"))
    )
    (net (code "53") (name "Net-(U7-RESETn)") (class "Default")
      (node (ref "R18") (pin "1") (pinfunction "1_1") (pintype "passive"))
      (node (ref "U7") (pin "43") (pinfunction "RESETn_43") (pintype "passive"))
    )
    (net (code "54") (name "Net-(U7-SCS)") (class "Default")
      (node (ref "R16") (pin "1") (pinfunction "1_1") (pintype "passive"))
      (node (ref "U7") (pin "45") (pinfunction "SCS_45") (pintype "passive"))
    )
    (net (code "55") (name "Net-(U7-V3P3)") (class "Default")
      (node (ref "C33") (pin "2") (pinfunction "2_2") (pintype "passive"))
      (node (ref "U7") (pin "16") (pinfunction "V3P3_16") (pintype "passive"))
    )
    (net (code "56") (name "Net-(U7-VCP)") (class "Default")
      (node (ref "C31") (pin "2") (pinfunction "2_2") (pintype "passive"))
      (node (ref "U7") (pin "9") (pinfunction "VCP_9") (pintype "passive"))
    )
    (net (code "57") (name "Net-(U8-CP1)") (class "Default")
      (node (ref "C54") (pin "2") (pinfunction "2_2") (pintype "passive"))
      (node (ref "U8") (pin "7") (pinfunction "CP1_7") (pintype "passive"))
    )
    (net (code "58") (name "Net-(U8-CP2)") (class "Default")
      (node (ref "C54") (pin "1") (pinfunction "1_1") (pintype "passive"))
      (node (ref "U8") (pin "8") (pinfunction "CP2_8") (pintype "passive"))
    )
    (net (code "59") (name "Net-(U8-RESETn)") (class "Default")
      (node (ref "R32") (pin "1") (pinfunction "1_1") (pintype "passive"))
      (node (ref "U8") (pin "43") (pinfunction "RESETn_43") (pintype "passive"))
    )
    (net (code "60") (name "Net-(U8-SCS)") (class "Default")
      (node (ref "R31") (pin "1") (pinfunction "1_1") (pintype "passive"))
      (node (ref "U8") (pin "45") (pinfunction "SCS_45") (pintype "passive"))
    )
    (net (code "61") (name "Net-(U8-V3P3)") (class "Default")
      (node (ref "C56") (pin "2") (pinfunction "2_2") (pintype "passive"))
      (node (ref "U8") (pin "16") (pinfunction "V3P3_16") (pintype "passive"))
    )
    (net (code "62") (name "Net-(U8-VCP)") (class "Default")
      (node (ref "C55") (pin "2") (pinfunction "2_2") (pintype "passive"))
      (node (ref "U8") (pin "9") (pinfunction "VCP_9") (pintype "passive"))
    )
    (net (code "63") (name "PGND") (class "Default")
      (node (ref "C22") (pin "2") (pinfunction "2_2") (pintype "passive"))
      (node (ref "C23") (pin "2") (pinfunction "2_2") (pintype "passive"))
      (node (ref "C24") (pin "1") (pinfunction "1_1") (pintype "passive"))
      (node (ref "C25") (pin "1") (pinfunction "1_1") (pintype "passive"))
      (node (ref "C32") (pin "1") (pinfunction "1_1") (pintype "passive"))
      (node (ref "C33") (pin "1") (pinfunction "1_1") (pintype "passive"))
      (node (ref "C51") (pin "2") (pinfunction "2_2") (pintype "passive"))
      (node (ref "C52") (pin "1") (pinfunction "1_1") (pintype "passive"))
      (node (ref "C56") (pin "1") (pinfunction "1_1") (pintype "passive"))
      (node (ref "U6") (pin "10") (pinfunction "PGND_10") (pintype "passive"))
      (node (ref "U6") (pin "11") (pinfunction "PGND_11") (pintype "passive"))
      (node (ref "U6") (pin "12") (pinfunction "PGND_12") (pintype "passive"))
      (node (ref "U6") (pin "13") (pinfunction "PGND_13") (pintype "passive"))
      (node (ref "U6") (pin "14") (pinfunction "PGND_14") (pintype "passive"))
      (node (ref "U6") (pin "15") (pinfunction "PGND_15") (pintype "passive"))
      (node (ref "U7") (pin "10") (pinfunction "PGND_10") (pintype "passive"))
      (node (ref "U7") (pin "11") (pinfunction "PGND_11") (pintype "passive"))
      (node (ref "U7") (pin "12") (pinfunction "PGND_12") (pintype "passive"))
      (node (ref "U7") (pin "13") (pinfunction "PGND_13") (pintype "passive"))
      (node (ref "U7") (pin "14") (pinfunction "PGND_14") (pintype "passive"))
      (node (ref "U7") (pin "15") (pinfunction "PGND_15") (pintype "passive"))
      (node (ref "U8") (pin "10") (pinfunction "PGND_10") (pintype "passive"))
      (node (ref "U8") (pin "11") (pinfunction "PGND_11") (pintype "passive"))
      (node (ref "U8") (pin "12") (pinfunction "PGND_12") (pintype "passive"))
      (node (ref "U8") (pin "13") (pinfunction "PGND_13") (pintype "passive"))
      (node (ref "U8") (pin "14") (pinfunction "PGND_14") (pintype "passive"))
      (node (ref "U8") (pin "15") (pinfunction "PGND_15") (pintype "passive"))
    )
    (net (code "64") (name "VCC3V3") (class "Default")
      (node (ref "R15") (pin "2") (pinfunction "2_2") (pintype "passive"))
      (node (ref "R16") (pin "2") (pinfunction "2_2") (pintype "passive"))
      (node (ref "R17") (pin "2") (pinfunction "2_2") (pintype "passive"))
      (node (ref "R18") (pin "2") (pinfunction "2_2") (pintype "passive"))
      (node (ref "R31") (pin "2") (pinfunction "2_2") (pintype "passive"))
      (node (ref "R32") (pin "2") (pinfunction "2_2") (pintype "passive"))
      (node (ref "R33") (pin "1") (pinfunction "1_1") (pintype "passive"))
      (node (ref "R34") (pin "1") (pinfunction "1_1") (pintype "passive"))
      (node (ref "R35") (pin "1") (pinfunction "1_1") (pintype "passive"))
      (node (ref "R36") (pin "1") (pinfunction "1_1") (pintype "passive"))
      (node (ref "R37") (pin "1") (pinfunction "1_1") (pintype "passive"))
      (node (ref "R38") (pin "1") (pinfunction "1_1") (pintype "passive"))
    )
    (net (code "65") (name "unconnected-(U6-NC-Pad6)") (class "Default")
      (node (ref "U6") (pin "6") (pinfunction "NC_6") (pintype "passive+no_connect"))
    )
    (net (code "66") (name "unconnected-(U6-NC-Pad40)") (class "Default")
      (node (ref "U6") (pin "40") (pinfunction "NC_40") (pintype "passive+no_connect"))
    )
    (net (code "67") (name "unconnected-(U6-NC-Pad41)") (class "Default")
      (node (ref "U6") (pin "41") (pinfunction "NC_41") (pintype "passive+no_connect"))
    )
    (net (code "68") (name "unconnected-(U6-NC-Pad44)") (class "Default")
      (node (ref "U6") (pin "44") (pinfunction "NC_44") (pintype "passive+no_connect"))
    )
    (net (code "69") (name "unconnected-(U6-SCLK-Pad33)") (class "Default")
      (node (ref "U6") (pin "33") (pinfunction "SCLK_33") (pintype "passive"))
    )
    (net (code "70") (name "unconnected-(U6-SDATA-Pad31)") (class "Default")
      (node (ref "U6") (pin "31") (pinfunction "SDATA_31") (pintype "passive"))
    )
    (net (code "71") (name "unconnected-(U6-SLEEPn-Pad42)") (class "Default")
      (node (ref "U6") (pin "42") (pinfunction "SLEEPn_42") (pintype "passive+no_connect"))
    )
    (net (code "72") (name "unconnected-(U6-SSTB-Pad30)") (class "Default")
      (node (ref "U6") (pin "30") (pinfunction "SSTB_30") (pintype "passive"))
    )
    (net (code "73") (name "unconnected-(U6-TEST-Pad19)") (class "Default")
      (node (ref "U6") (pin "19") (pinfunction "TEST_19") (pintype "passive+no_connect"))
    )
    (net (code "74") (name "unconnected-(U6-TEST-Pad28)") (class "Default")
      (node (ref "U6") (pin "28") (pinfunction "TEST_28") (pintype "passive+no_connect"))
    )
    (net (code "75") (name "unconnected-(U6-TEST-Pad29)") (class "Default")
      (node (ref "U6") (pin "29") (pinfunction "TEST_29") (pintype "passive+no_connect"))
    )
    (net (code "76") (name "unconnected-(U6-TEST-Pad32)") (class "Default")
      (node (ref "U6") (pin "32") (pinfunction "TEST_32") (pintype "passive+no_connect"))
    )
    (net (code "77") (name "unconnected-(U7-NC-Pad6)") (class "Default")
      (node (ref "U7") (pin "6") (pinfunction "NC_6") (pintype "passive+no_connect"))
    )
    (net (code "78") (name "unconnected-(U7-NC-Pad40)") (class "Default")
      (node (ref "U7") (pin "40") (pinfunction "NC_40") (pintype "passive+no_connect"))
    )
    (net (code "79") (name "unconnected-(U7-NC-Pad41)") (class "Default")
      (node (ref "U7") (pin "41") (pinfunction "NC_41") (pintype "passive+no_connect"))
    )
    (net (code "80") (name "unconnected-(U7-NC-Pad44)") (class "Default")
      (node (ref "U7") (pin "44") (pinfunction "NC_44") (pintype "passive+no_connect"))
    )
    (net (code "81") (name "unconnected-(U7-SCLK-Pad33)") (class "Default")
      (node (ref "U7") (pin "33") (pinfunction "SCLK_33") (pintype "passive"))
    )
    (net (code "82") (name "unconnected-(U7-SDATA-Pad31)") (class "Default")
      (node (ref "U7") (pin "31") (pinfunction "SDATA_31") (pintype "passive"))
    )
    (net (code "83") (name "unconnected-(U7-SLEEPn-Pad42)") (class "Default")
      (node (ref "U7") (pin "42") (pinfunction "SLEEPn_42") (pintype "passive+no_connect"))
    )
    (net (code "84") (name "unconnected-(U7-SSTB-Pad30)") (class "Default")
      (node (ref "U7") (pin "30") (pinfunction "SSTB_30") (pintype "passive"))
    )
    (net (code "85") (name "unconnected-(U7-TEST-Pad19)") (class "Default")
      (node (ref "U7") (pin "19") (pinfunction "TEST_19") (pintype "passive+no_connect"))
    )
    (net (code "86") (name "unconnected-(U7-TEST-Pad28)") (class "Default")
      (node (ref "U7") (pin "28") (pinfunction "TEST_28") (pintype "passive+no_connect"))
    )
    (net (code "87") (name "unconnected-(U7-TEST-Pad29)") (class "Default")
      (node (ref "U7") (pin "29") (pinfunction "TEST_29") (pintype "passive+no_connect"))
    )
    (net (code "88") (name "unconnected-(U7-TEST-Pad32)") (class "Default")
      (node (ref "U7") (pin "32") (pinfunction "TEST_32") (pintype "passive+no_connect"))
    )
    (net (code "89") (name "unconnected-(U8-NC-Pad6)") (class "Default")
      (node (ref "U8") (pin "6") (pinfunction "NC_6") (pintype "passive+no_connect"))
    )
    (net (code "90") (name "unconnected-(U8-NC-Pad40)") (class "Default")
      (node (ref "U8") (pin "40") (pinfunction "NC_40") (pintype "passive+no_connect"))
    )
    (net (code "91") (name "unconnected-(U8-NC-Pad41)") (class "Default")
      (node (ref "U8") (pin "41") (pinfunction "NC_41") (pintype "passive+no_connect"))
    )
    (net (code "92") (name "unconnected-(U8-NC-Pad44)") (class "Default")
      (node (ref "U8") (pin "44") (pinfunction "NC_44") (pintype "passive+no_connect"))
    )
    (net (code "93") (name "unconnected-(U8-SCLK-Pad33)") (class "Default")
      (node (ref "U8") (pin "33") (pinfunction "SCLK_33") (pintype "passive"))
    )
    (net (code "94") (name "unconnected-(U8-SDATA-Pad31)") (class "Default")
      (node (ref "U8") (pin "31") (pinfunction "SDATA_31") (pintype "passive"))
    )
    (net (code "95") (name "unconnected-(U8-SLEEPn-Pad42)") (class "Default")
      (node (ref "U8") (pin "42") (pinfunction "SLEEPn_42") (pintype "passive+no_connect"))
    )
    (net (code "96") (name "unconnected-(U8-SSTB-Pad30)") (class "Default")
      (node (ref "U8") (pin "30") (pinfunction "SSTB_30") (pintype "passive"))
    )
    (net (code "97") (name "unconnected-(U8-TEST-Pad19)") (class "Default")
      (node (ref "U8") (pin "19") (pinfunction "TEST_19") (pintype "passive+no_connect"))
    )
    (net (code "98") (name "unconnected-(U8-TEST-Pad28)") (class "Default")
      (node (ref "U8") (pin "28") (pinfunction "TEST_28") (pintype "passive+no_connect"))
    )
    (net (code "99") (name "unconnected-(U8-TEST-Pad29)") (class "Default")
      (node (ref "U8") (pin "29") (pinfunction "TEST_29") (pintype "passive+no_connect"))
    )
    (net (code "100") (name "unconnected-(U8-TEST-Pad32)") (class "Default")
      (node (ref "U8") (pin "32") (pinfunction "TEST_32") (pintype "passive+no_connect"))
    )
  )
)
